# LTE.net
KiCad netlist of a schematic drawn in Altium Designer
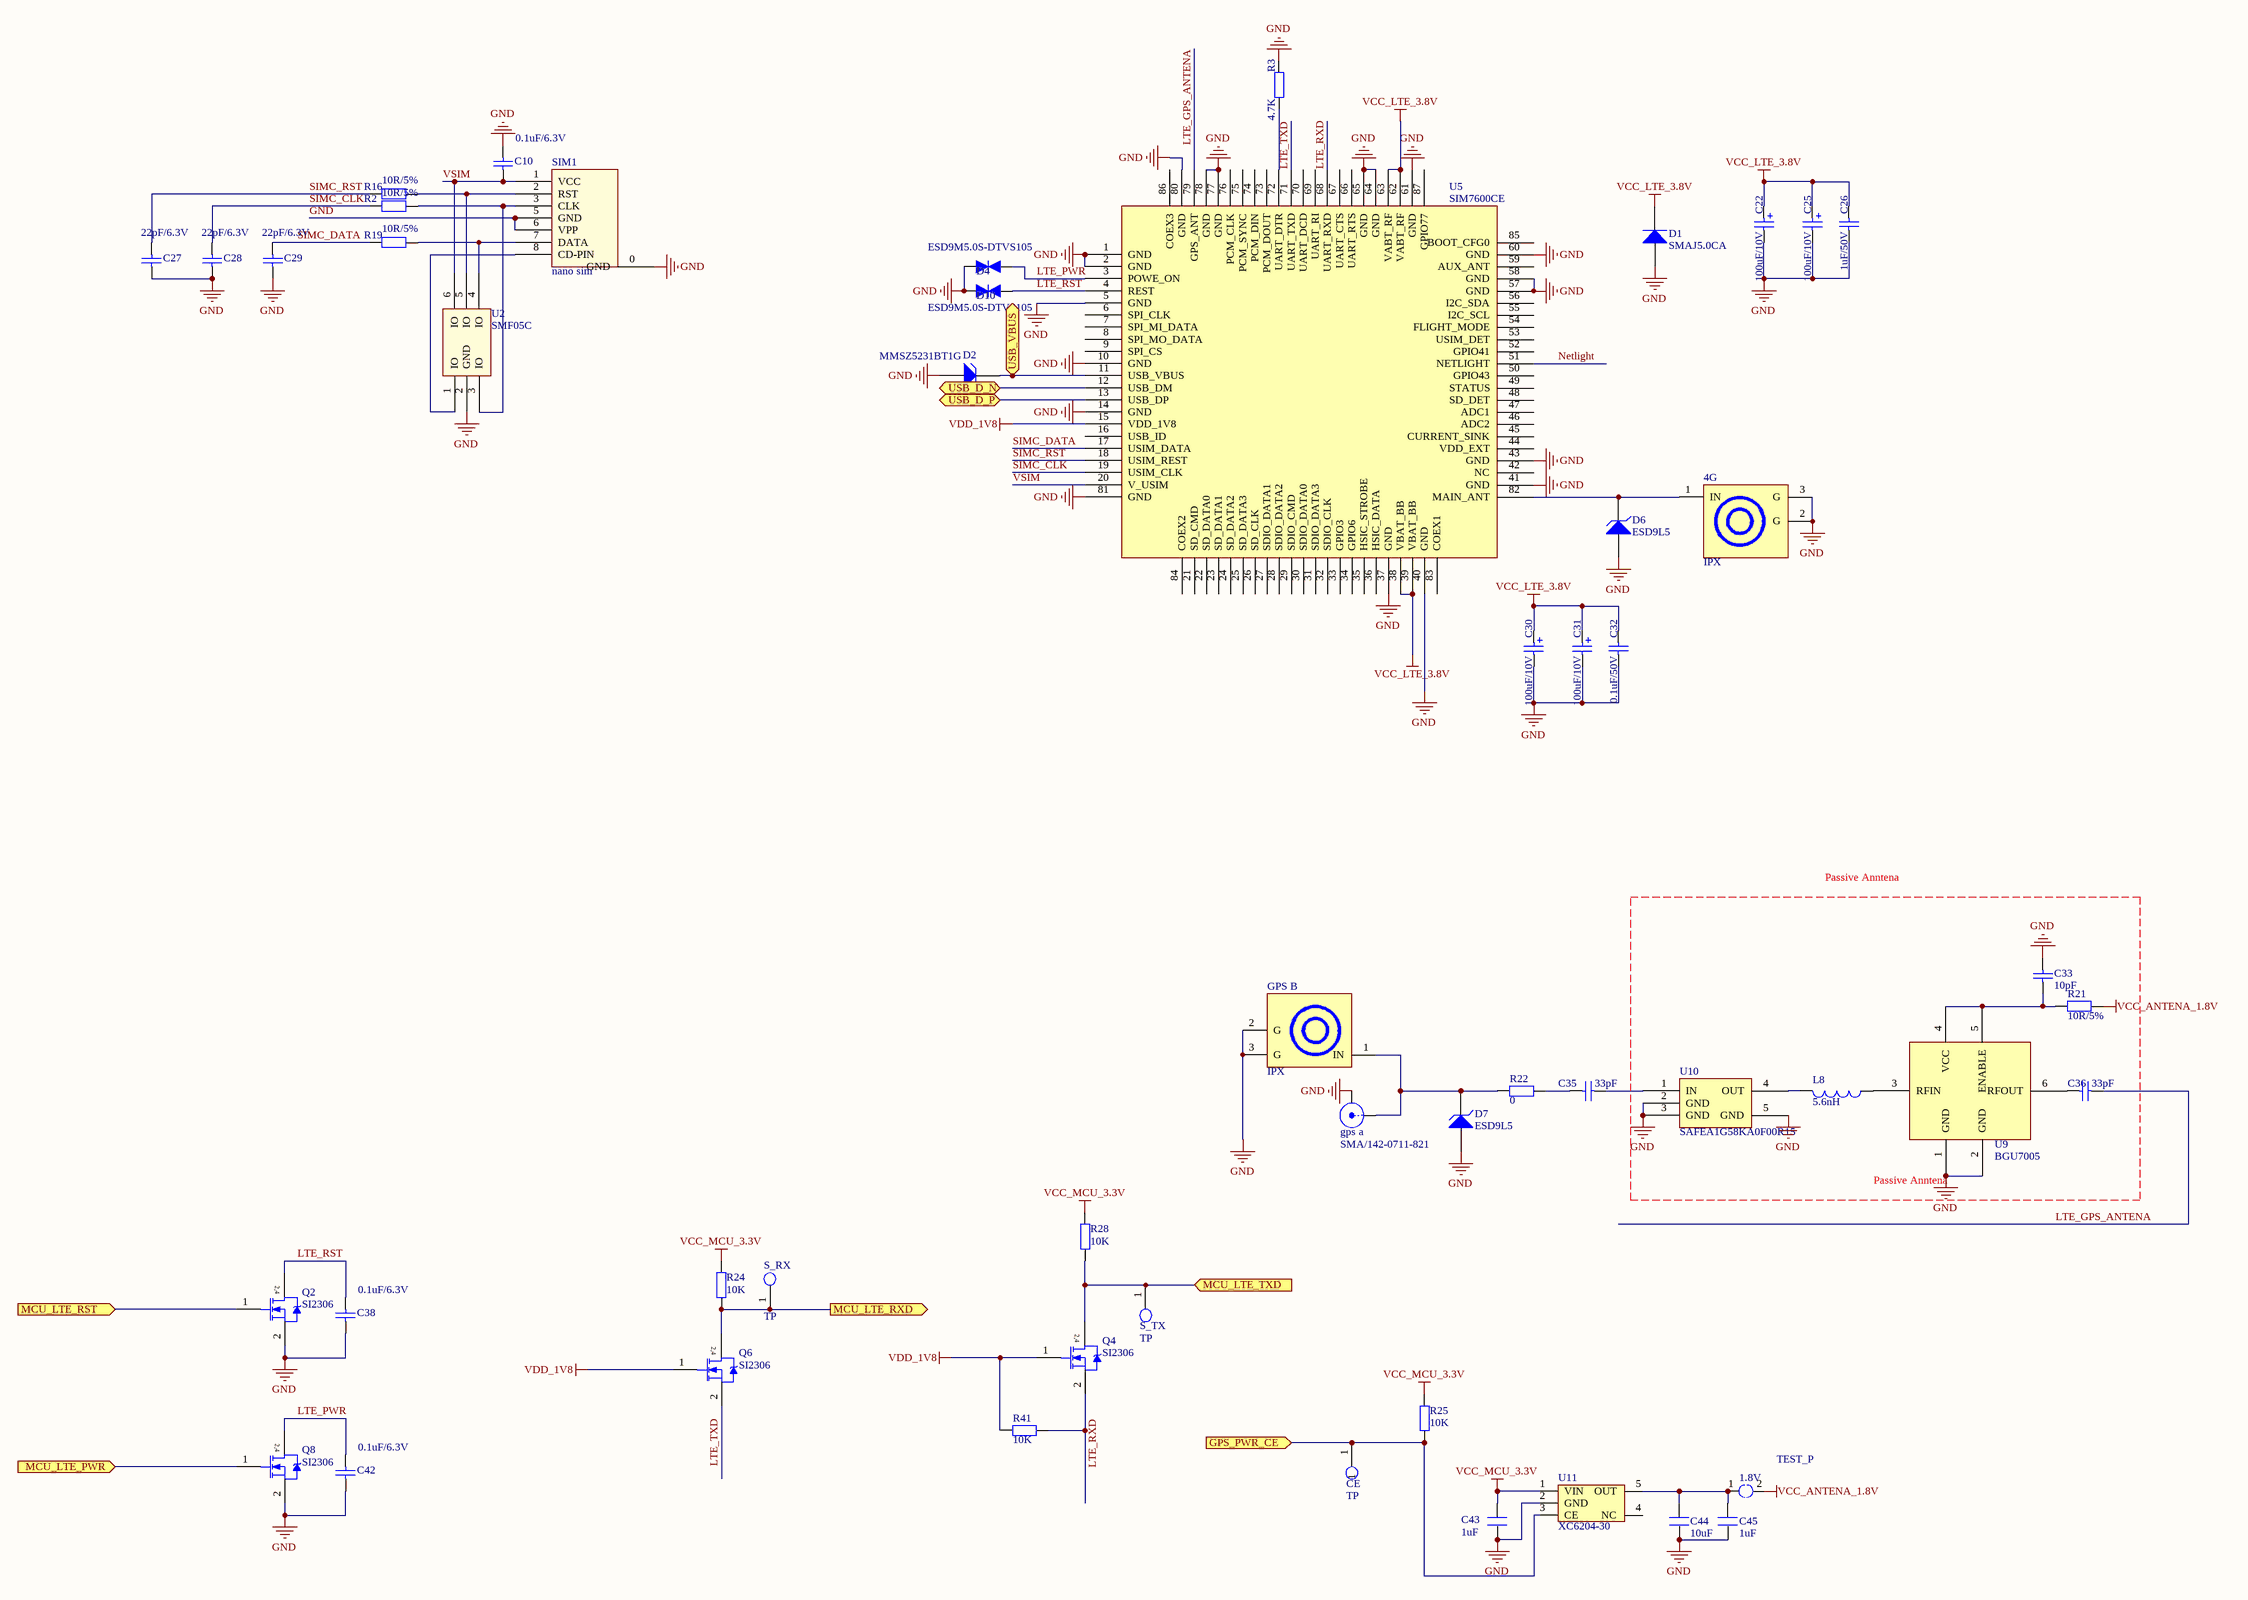
[diagram p0: LTE.SchDoc]

(export (version "E")
  (design (tool "Eeschema 10.0.6"))
  (components
    (comp (ref "1.8V")
      (value "TEST_P")
      (footprint "Pcblib_20110825:TP_High PWR")
      (libsource (lib "Schlib_20110825") (part "TEST_P"))
    )
    (comp (ref "4G")
      (value "IPX")
      (footprint "Pcblib_20110825:ECT8180001581")
      (description "MCU")
      (libsource (lib "MCU") (part "IPX"))
    )
    (comp (ref "C10")
      (value "0.1uF/6.3V")
      (footprint "Pcblib_20110825:0603C")
      (description "Capacitor")
      (fields (field (name "PUBLISHER") "Altium Limited"))
      (libsource (lib "Miscellaneous Devices") (part "Cap"))
    )
    (comp (ref "C22")
      (value "100uF/10V")
      (footprint "1210E")
      (description "Polarized Capacitor (Axial)")
      (fields (field (name "PUBLISHER") "Altium Limited"))
      (libsource (lib "Miscellaneous Devices") (part "Cap Pol2"))
    )
    (comp (ref "C25")
      (value "100uF/10V")
      (footprint "1210E")
      (description "Polarized Capacitor (Axial)")
      (fields (field (name "PUBLISHER") "Altium Limited"))
      (libsource (lib "Miscellaneous Devices") (part "Cap Pol2"))
    )
    (comp (ref "C26")
      (value "1uF/50V")
      (footprint "0603C")
      (description "Capacitor")
      (fields (field (name "PUBLISHER") "Altium Limited"))
      (libsource (lib "Miscellaneous Devices") (part "Cap"))
    )
    (comp (ref "C27")
      (value "22pF/6.3V")
      (footprint "Pcblib_20110825:0603C")
      (description "Capacitor")
      (fields (field (name "PUBLISHER") "Altium Limited"))
      (libsource (lib "Miscellaneous Devices") (part "Cap"))
    )
    (comp (ref "C28")
      (value "22pF/6.3V")
      (footprint "Pcblib_20110825:0603C")
      (description "Capacitor")
      (fields (field (name "PUBLISHER") "Altium Limited"))
      (libsource (lib "Miscellaneous Devices") (part "Cap"))
    )
    (comp (ref "C29")
      (value "22pF/6.3V")
      (footprint "Pcblib_20110825:0603C")
      (description "Capacitor")
      (fields (field (name "PUBLISHER") "Altium Limited"))
      (libsource (lib "Miscellaneous Devices") (part "Cap"))
    )
    (comp (ref "C30")
      (value "100uF/10V")
      (footprint "1210E")
      (description "Polarized Capacitor (Axial)")
      (fields (field (name "PUBLISHER") "Altium Limited"))
      (libsource (lib "Miscellaneous Devices") (part "Cap Pol2"))
    )
    (comp (ref "C31")
      (value "100uF/10V")
      (footprint "1210E")
      (description "Polarized Capacitor (Axial)")
      (fields (field (name "PUBLISHER") "Altium Limited"))
      (libsource (lib "Miscellaneous Devices") (part "Cap Pol2"))
    )
    (comp (ref "C32")
      (value "0.1uF/50V")
      (footprint "0603C")
      (description "Capacitor")
      (fields (field (name "PUBLISHER") "Altium Limited"))
      (libsource (lib "Miscellaneous Devices") (part "Cap"))
    )
    (comp (ref "C33")
      (value "10pF")
      (footprint "Pcblib_20110825:0603C")
      (description "Capacitor")
      (fields (field (name "PUBLISHER") "Altium Limited"))
      (libsource (lib "Miscellaneous Devices") (part "Cap"))
    )
    (comp (ref "C35")
      (value "33pF")
      (footprint "Pcblib_20110825:0603C")
      (description "Capacitor")
      (fields (field (name "PUBLISHER") "Altium Limited"))
      (libsource (lib "Miscellaneous Devices") (part "Cap"))
    )
    (comp (ref "C36")
      (value "33pF")
      (footprint "Pcblib_20110825:0603C")
      (description "Capacitor")
      (fields (field (name "PUBLISHER") "Altium Limited"))
      (libsource (lib "Miscellaneous Devices") (part "Cap"))
    )
    (comp (ref "C38")
      (value "0.1uF/6.3V")
      (footprint "Pcblib_20110825:0603C")
      (description "Capacitor")
      (fields (field (name "PUBLISHER") "Altium Limited"))
      (libsource (lib "Miscellaneous Devices") (part "Cap"))
    )
    (comp (ref "C42")
      (value "0.1uF/6.3V")
      (footprint "Pcblib_20110825:0603C")
      (description "Capacitor")
      (fields (field (name "PUBLISHER") "Altium Limited"))
      (libsource (lib "Miscellaneous Devices") (part "Cap"))
    )
    (comp (ref "C43") (value "1uF") (footprint "0603C") (libsource (lib "MiniFly ") (part "C")))
    (comp (ref "C44") (value "10uF") (footprint "0603C") (libsource (lib "MiniFly ") (part "C")))
    (comp (ref "C45") (value "1uF") (footprint "0402C") (libsource (lib "MiniFly ") (part "C")))
    (comp (ref "CE") (value "TP") (footprint "Pcblib_20110825:TPD") (libsource (lib "") (part "TP_1")))
    (comp (ref "D1")
      (value "SMAJ5.0CA")
      (footprint "SMA")
      (description "Default Diode")
      (fields (field (name "PUBLISHER") "Altium Limited"))
      (libsource (lib "Miscellaneous Devices") (part "Diode"))
    )
    (comp (ref "D2")
      (value "MMSZ5231BT1G")
      (footprint "Pcblib_20110825:SOD123")
      (description "Zener Diode")
      (fields (field (name "PUBLISHER") "Altium Limited"))
      (libsource (lib "Miscellaneous Devices") (part "D Zener"))
    )
    (comp (ref "D4")
      (value "ESD9M5.0S-DTVS105")
      (footprint "SOD923")
      (libsource (lib "Schlib_20110825") (part "ESD9M5.0S-DTVS105"))
    )
    (comp (ref "D6")
      (value "ESD9L5")
      (footprint "Pcblib_20110825:SOD923")
      (description "Zener Diode")
      (fields (field (name "PUBLISHER") "Altium Limited"))
      (libsource (lib "Miscellaneous Devices") (part "D Zener"))
    )
    (comp (ref "D7")
      (value "ESD9L5")
      (footprint "Pcblib_20110825:SOD923")
      (description "Zener Diode")
      (fields (field (name "PUBLISHER") "Altium Limited"))
      (libsource (lib "Miscellaneous Devices") (part "D Zener"))
    )
    (comp (ref "D10")
      (value "ESD9M5.0S-DTVS105")
      (footprint "SOD923")
      (libsource (lib "Schlib_20110825") (part "ESD9M5.0S-DTVS105"))
    )
    (comp (ref "gps a")
      (value "SMA/142-0711-821")
      (footprint "Pcblib_20110825:SMA END LAUNCH JACK RECEPTACLE SHORT")
      (description "SMA Straight Connector")
      (fields (field (name "PUBLISHER") "Altium Limited"))
      (libsource (lib "SX1276_e266v02a") (part "SMA"))
    )
    (comp (ref "GPS B")
      (value "IPX")
      (footprint "Pcblib_20110825:ECT8180001581")
      (description "MCU")
      (libsource (lib "") (part "IPX_1"))
    )
    (comp (ref "L8")
      (value "5.6nH")
      (footprint "INDC1005AL")
      (description "Inductor")
      (fields (field (name "PUBLISHER") "Altium Limited"))
      (libsource (lib "Miscellaneous Devices") (part "Inductor"))
    )
    (comp (ref "Q2")
      (value "SI2306")
      (footprint "Pcblib_20110825:SOT23-3")
      (description "BUK92150-55A")
      (fields (field (name "PUBLISHER") "Altium Limited"))
      (libsource (lib "Schlib1") (part "BUK92150-55A"))
    )
    (comp (ref "Q4")
      (value "SI2306")
      (footprint "Pcblib_20110825:SOT23-3")
      (description "BUK92150-55A")
      (fields (field (name "PUBLISHER") "Altium Limited"))
      (libsource (lib "Schlib1") (part "BUK92150-55A"))
    )
    (comp (ref "Q6")
      (value "SI2306")
      (footprint "Pcblib_20110825:SOT23-3")
      (description "BUK92150-55A")
      (fields (field (name "PUBLISHER") "Altium Limited"))
      (libsource (lib "Schlib1") (part "BUK92150-55A"))
    )
    (comp (ref "Q8")
      (value "SI2306")
      (footprint "Pcblib_20110825:SOT23-3")
      (description "BUK92150-55A")
      (fields (field (name "PUBLISHER") "Altium Limited"))
      (libsource (lib "Schlib1") (part "BUK92150-55A"))
    )
    (comp (ref "R2")
      (value "10R/5%")
      (footprint "Pcblib_20110825:0603R")
      (description "Resistor")
      (fields (field (name "PUBLISHER") "Altium Limited"))
      (libsource (lib "") (part "Res2_1"))
    )
    (comp (ref "R3")
      (value "4.7K")
      (footprint "Pcblib_20110825:0603R")
      (description "Resistor")
      (fields (field (name "PUBLISHER") "Altium Limited"))
      (libsource (lib "") (part "Res2_3"))
    )
    (comp (ref "R16")
      (value "10R/5%")
      (footprint "Pcblib_20110825:0603R")
      (description "Resistor")
      (fields (field (name "PUBLISHER") "Altium Limited"))
      (libsource (lib "") (part "Res2_1"))
    )
    (comp (ref "R19")
      (value "10R/5%")
      (footprint "Pcblib_20110825:0603R")
      (description "Resistor")
      (fields (field (name "PUBLISHER") "Altium Limited"))
      (libsource (lib "") (part "Res2_1"))
    )
    (comp (ref "R21")
      (value "10R/5%")
      (footprint "Pcblib_20110825:0603R")
      (description "Resistor")
      (fields (field (name "PUBLISHER") "Altium Limited"))
      (libsource (lib "Miscellaneous Devices") (part "Res2"))
    )
    (comp (ref "R22")
      (value "0")
      (footprint "Pcblib_20110825:0603R")
      (description "Resistor")
      (fields (field (name "PUBLISHER") "Altium Limited"))
      (libsource (lib "Miscellaneous Devices") (part "Res2"))
    )
    (comp (ref "R24")
      (value "10K")
      (footprint "Pcblib_20110825:0603R")
      (description "Resistor")
      (fields (field (name "PUBLISHER") "Altium Limited"))
      (libsource (lib "") (part "Res2_3"))
    )
    (comp (ref "R25")
      (value "10K")
      (footprint "Pcblib_20110825:0603R")
      (description "Resistor")
      (fields (field (name "PUBLISHER") "Altium Limited"))
      (libsource (lib "") (part "Res2_2"))
    )
    (comp (ref "R28")
      (value "10K")
      (footprint "Pcblib_20110825:0603R")
      (description "Resistor")
      (fields (field (name "PUBLISHER") "Altium Limited"))
      (libsource (lib "") (part "Res2_2"))
    )
    (comp (ref "R41")
      (value "10K")
      (footprint "Pcblib_20110825:0603R")
      (description "Resistor")
      (fields (field (name "PUBLISHER") "Altium Limited"))
      (libsource (lib "") (part "Res2_1"))
    )
    (comp (ref "SIM1") (value "nano sim") (footprint "Nano SIM") (libsource (lib "lm") (part "nano sim")))
    (comp (ref "S_RX")
      (value "TP")
      (footprint "Pcblib_20110825:TPD")
      (libsource (lib "Schlib_20110825") (part "TP"))
    )
    (comp (ref "S_TX")
      (value "TP")
      (footprint "Pcblib_20110825:TPD")
      (libsource (lib "Schlib_20110825") (part "TP"))
    )
    (comp (ref "U2") (value "SMF05C") (footprint "SC70-6L") (libsource (lib "lm") (part "SMF05C")))
    (comp (ref "U5")
      (value "SIM7600CE")
      (footprint "SIM7600CE")
      (libsource (lib "DTU_20161116_ZM_V1.1") (part "SIM7600CE"))
    )
    (comp (ref "U9")
      (value "BGU7005")
      (footprint "BGU7005")
      (libsource (lib "Schlib_20110825") (part "BGU7005"))
    )
    (comp (ref "U10")
      (value "SAFEA1G58KA0F00R15")
      (footprint "SAFEA1G58KA0F00R15")
      (libsource (lib "Schlib_20110825") (part "SAFEA1G58KA0F00R15"))
    )
    (comp (ref "U11")
      (value "XC6204-30")
      (footprint "SOT23-5(DBV)")
      (libsource (lib "MiniFly ") (part "XC6204"))
    )
  )
  (nets
    (net (code "1") (name "/GPS_PWR_CE") (class "Default")
      (node (ref "CE") (pin "1") (pinfunction "1_1") (pintype "passive"))
      (node (ref "R25") (pin "1") (pinfunction "1_1") (pintype "passive"))
      (node (ref "U11") (pin "3") (pinfunction "CE_3") (pintype "passive"))
    )
    (net (code "2") (name "/LTE_GPS_ANTENA") (class "Default")
      (node (ref "C36") (pin "2") (pinfunction "2_2") (pintype "passive"))
      (node (ref "U5") (pin "79") (pinfunction "GPS_ANT_79") (pintype "passive"))
    )
    (net (code "3") (name "/LTE_PWR") (class "Default")
      (node (ref "C42") (pin "1") (pinfunction "1_1") (pintype "passive"))
      (node (ref "D4") (pin "2") (pinfunction "K_2") (pintype "passive"))
      (node (ref "Q8") (pin "3") (pinfunction "D_3") (pintype "passive"))
      (node (ref "U5") (pin "3") (pinfunction "POWE_ON_3") (pintype "passive"))
    )
    (net (code "4") (name "/LTE_RST") (class "Default")
      (node (ref "C38") (pin "1") (pinfunction "1_1") (pintype "passive"))
      (node (ref "D10") (pin "2") (pinfunction "K_2") (pintype "passive"))
      (node (ref "Q2") (pin "3") (pinfunction "D_3") (pintype "passive"))
      (node (ref "U5") (pin "4") (pinfunction "REST_4") (pintype "passive"))
    )
    (net (code "5") (name "/LTE_RXD") (class "Default")
      (node (ref "Q4") (pin "2") (pinfunction "S_2") (pintype "passive"))
      (node (ref "R41") (pin "1") (pinfunction "1_1") (pintype "passive"))
      (node (ref "U5") (pin "68") (pinfunction "UART_RXD_68") (pintype "passive"))
    )
    (net (code "6") (name "/LTE_TXD") (class "Default")
      (node (ref "Q6") (pin "2") (pinfunction "S_2") (pintype "passive"))
      (node (ref "U5") (pin "71") (pinfunction "UART_TXD_71") (pintype "passive"))
    )
    (net (code "7") (name "/MCU_LTE_PWR") (class "Default")
      (node (ref "Q8") (pin "1") (pinfunction "G_1") (pintype "passive"))
    )
    (net (code "8") (name "/MCU_LTE_RST") (class "Default")
      (node (ref "Q2") (pin "1") (pinfunction "G_1") (pintype "passive"))
    )
    (net (code "9") (name "/MCU_LTE_RXD") (class "Default")
      (node (ref "Q6") (pin "3") (pinfunction "D_3") (pintype "passive"))
      (node (ref "R24") (pin "2") (pinfunction "2_2") (pintype "passive"))
      (node (ref "S_RX") (pin "1") (pintype "passive"))
    )
    (net (code "10") (name "/MCU_LTE_TXD") (class "Default")
      (node (ref "Q4") (pin "3") (pinfunction "D_3") (pintype "passive"))
      (node (ref "R28") (pin "1") (pinfunction "1_1") (pintype "passive"))
      (node (ref "S_TX") (pin "1") (pintype "passive"))
    )
    (net (code "11") (name "/Netlight") (class "Default")
      (node (ref "U5") (pin "51") (pinfunction "NETLIGHT_51") (pintype "passive"))
    )
    (net (code "12") (name "/SIMC_CLK") (class "Default")
      (node (ref "C28") (pin "1") (pinfunction "1_1") (pintype "passive"))
      (node (ref "R2") (pin "2") (pinfunction "2_2") (pintype "passive"))
      (node (ref "U5") (pin "19") (pinfunction "USIM_CLK_19") (pintype "passive"))
    )
    (net (code "13") (name "/SIMC_DATA") (class "Default")
      (node (ref "C29") (pin "1") (pinfunction "1_1") (pintype "passive"))
      (node (ref "R19") (pin "2") (pinfunction "2_2") (pintype "passive"))
      (node (ref "U5") (pin "17") (pinfunction "USIM_DATA_17") (pintype "passive"))
    )
    (net (code "14") (name "/SIMC_RST") (class "Default")
      (node (ref "C27") (pin "1") (pinfunction "1_1") (pintype "passive"))
      (node (ref "R16") (pin "2") (pinfunction "2_2") (pintype "passive"))
      (node (ref "U5") (pin "18") (pinfunction "USIM_REST_18") (pintype "passive"))
    )
    (net (code "15") (name "/USB_D_N") (class "Default")
      (node (ref "U5") (pin "12") (pinfunction "USB_DM_12") (pintype "passive"))
    )
    (net (code "16") (name "/USB_D_P") (class "Default")
      (node (ref "U5") (pin "13") (pinfunction "USB_DP_13") (pintype "passive"))
    )
    (net (code "17") (name "/USB_VBUS") (class "Default")
      (node (ref "D2") (pin "K") (pinfunction "K_K") (pintype "passive"))
      (node (ref "U5") (pin "11") (pinfunction "USB_VBUS_11") (pintype "passive"))
    )
    (net (code "18") (name "/VSIM") (class "Default")
      (node (ref "C10") (pin "2") (pinfunction "2_2") (pintype "passive"))
      (node (ref "SIM1") (pin "1") (pinfunction "VCC_1") (pintype "passive"))
      (node (ref "U2") (pin "6") (pinfunction "IO_6") (pintype "passive"))
      (node (ref "U5") (pin "20") (pinfunction "V_USIM_20") (pintype "passive"))
    )
    (net (code "19") (name "GND") (class "Default")
      (node (ref "4G") (pin "2") (pinfunction "G_2") (pintype "passive"))
      (node (ref "4G") (pin "3") (pinfunction "G_3") (pintype "passive"))
      (node (ref "C10") (pin "1") (pinfunction "1_1") (pintype "passive"))
      (node (ref "C22") (pin "2") (pinfunction "2_2") (pintype "passive"))
      (node (ref "C25") (pin "2") (pinfunction "2_2") (pintype "passive"))
      (node (ref "C26") (pin "2") (pinfunction "2_2") (pintype "passive"))
      (node (ref "C27") (pin "2") (pinfunction "2_2") (pintype "passive"))
      (node (ref "C28") (pin "2") (pinfunction "2_2") (pintype "passive"))
      (node (ref "C29") (pin "2") (pinfunction "2_2") (pintype "passive"))
      (node (ref "C30") (pin "2") (pinfunction "2_2") (pintype "passive"))
      (node (ref "C31") (pin "2") (pinfunction "2_2") (pintype "passive"))
      (node (ref "C32") (pin "2") (pinfunction "2_2") (pintype "passive"))
      (node (ref "C33") (pin "2") (pinfunction "2_2") (pintype "passive"))
      (node (ref "C38") (pin "2") (pinfunction "2_2") (pintype "passive"))
      (node (ref "C42") (pin "2") (pinfunction "2_2") (pintype "passive"))
      (node (ref "C43") (pin "1") (pintype "passive"))
      (node (ref "C44") (pin "1") (pintype "passive"))
      (node (ref "C45") (pin "1") (pintype "passive"))
      (node (ref "D1") (pin "1") (pinfunction "A_1") (pintype "passive"))
      (node (ref "D10") (pin "1") (pinfunction "A_1") (pintype "passive"))
      (node (ref "D2") (pin "A") (pinfunction "A_A") (pintype "passive"))
      (node (ref "D4") (pin "1") (pinfunction "A_1") (pintype "passive"))
      (node (ref "D6") (pin "A") (pinfunction "A_A") (pintype "passive"))
      (node (ref "D7") (pin "A") (pinfunction "A_A") (pintype "passive"))
      (node (ref "GPS B") (pin "2") (pinfunction "G_2") (pintype "passive"))
      (node (ref "GPS B") (pin "3") (pinfunction "G_3") (pintype "passive"))
      (node (ref "Q2") (pin "2") (pinfunction "S_2") (pintype "passive"))
      (node (ref "Q8") (pin "2") (pinfunction "S_2") (pintype "passive"))
      (node (ref "R3") (pin "1") (pinfunction "1_1") (pintype "passive"))
      (node (ref "SIM1") (pin "0") (pinfunction "GND_0") (pintype "passive"))
      (node (ref "SIM1") (pin "5") (pinfunction "GND_5") (pintype "passive"))
      (node (ref "SIM1") (pin "6") (pinfunction "VPP_6") (pintype "passive"))
      (node (ref "U10") (pin "2") (pinfunction "GND_2") (pintype "passive"))
      (node (ref "U10") (pin "3") (pinfunction "GND_3") (pintype "passive"))
      (node (ref "U10") (pin "5") (pinfunction "GND_5") (pintype "passive"))
      (node (ref "U11") (pin "2") (pinfunction "GND_2") (pintype "passive"))
      (node (ref "U2") (pin "2") (pinfunction "GND_2") (pintype "passive"))
      (node (ref "U5") (pin "1") (pinfunction "GND_1") (pintype "passive"))
      (node (ref "U5") (pin "10") (pinfunction "GND_10") (pintype "passive"))
      (node (ref "U5") (pin "14") (pinfunction "GND_14") (pintype "passive"))
      (node (ref "U5") (pin "2") (pinfunction "GND_2") (pintype "passive"))
      (node (ref "U5") (pin "37") (pinfunction "GND_37") (pintype "passive"))
      (node (ref "U5") (pin "40") (pinfunction "GND_40") (pintype "passive"))
      (node (ref "U5") (pin "41") (pinfunction "GND_41") (pintype "passive"))
      (node (ref "U5") (pin "43") (pinfunction "GND_43") (pintype "passive"))
      (node (ref "U5") (pin "5") (pinfunction "GND_5") (pintype "passive"))
      (node (ref "U5") (pin "57") (pinfunction "GND_57") (pintype "passive"))
      (node (ref "U5") (pin "58") (pinfunction "GND_58") (pintype "passive"))
      (node (ref "U5") (pin "60") (pinfunction "GND_60") (pintype "passive"))
      (node (ref "U5") (pin "61") (pinfunction "GND_61") (pintype "passive"))
      (node (ref "U5") (pin "64") (pinfunction "GND_64") (pintype "passive"))
      (node (ref "U5") (pin "65") (pinfunction "GND_65") (pintype "passive"))
      (node (ref "U5") (pin "77") (pinfunction "GND_77") (pintype "passive"))
      (node (ref "U5") (pin "78") (pinfunction "GND_78") (pintype "passive"))
      (node (ref "U5") (pin "80") (pinfunction "GND_80") (pintype "passive"))
      (node (ref "U5") (pin "81") (pinfunction "GND_81") (pintype "passive"))
      (node (ref "U9") (pin "1") (pinfunction "GND_1") (pintype "passive"))
      (node (ref "U9") (pin "2") (pinfunction "GND_2") (pintype "passive"))
      (node (ref "gps a") (pin "2") (pinfunction "GND_2") (pintype "passive"))
    )
    (net (code "20") (name "Net-(4G-IN)") (class "Default")
      (node (ref "4G") (pin "1") (pinfunction "IN_1") (pintype "passive"))
      (node (ref "D6") (pin "K") (pinfunction "K_K") (pintype "passive"))
      (node (ref "U5") (pin "82") (pinfunction "MAIN_ANT_82") (pintype "passive"))
    )
    (net (code "21") (name "Net-(C35-Pad1)") (class "Default")
      (node (ref "C35") (pin "1") (pinfunction "1_1") (pintype "passive"))
      (node (ref "R22") (pin "2") (pinfunction "2_2") (pintype "passive"))
    )
    (net (code "22") (name "Net-(GPS B-IN)") (class "Default")
      (node (ref "D7") (pin "K") (pinfunction "K_K") (pintype "passive"))
      (node (ref "GPS B") (pin "1") (pinfunction "IN_1") (pintype "passive"))
      (node (ref "R22") (pin "1") (pinfunction "1_1") (pintype "passive"))
      (node (ref "gps a") (pin "1") (pinfunction "Signal_1") (pintype "passive"))
    )
    (net (code "23") (name "Net-(SIM1-CD-PIN)") (class "Default")
      (node (ref "SIM1") (pin "8") (pinfunction "CD-PIN_8") (pintype "passive"))
      (node (ref "U2") (pin "1") (pinfunction "IO_1") (pintype "passive"))
    )
    (net (code "24") (name "Net-(SIM1-CLK)") (class "Default")
      (node (ref "R2") (pin "1") (pinfunction "1_1") (pintype "passive"))
      (node (ref "SIM1") (pin "3") (pinfunction "CLK_3") (pintype "passive"))
      (node (ref "U2") (pin "3") (pinfunction "IO_3") (pintype "passive"))
    )
    (net (code "25") (name "Net-(SIM1-DATA)") (class "Default")
      (node (ref "R19") (pin "1") (pinfunction "1_1") (pintype "passive"))
      (node (ref "SIM1") (pin "7") (pinfunction "DATA_7") (pintype "passive"))
      (node (ref "U2") (pin "4") (pinfunction "IO_4") (pintype "passive"))
    )
    (net (code "26") (name "Net-(SIM1-RST)") (class "Default")
      (node (ref "R16") (pin "1") (pinfunction "1_1") (pintype "passive"))
      (node (ref "SIM1") (pin "2") (pinfunction "RST_2") (pintype "passive"))
      (node (ref "U2") (pin "5") (pinfunction "IO_5") (pintype "passive"))
    )
    (net (code "27") (name "Net-(U5-UART_DTR)") (class "Default")
      (node (ref "R3") (pin "2") (pinfunction "2_2") (pintype "passive"))
      (node (ref "U5") (pin "72") (pinfunction "UART_DTR_72") (pintype "passive"))
    )
    (net (code "28") (name "Net-(U9-ENABLE)") (class "Default")
      (node (ref "C33") (pin "1") (pinfunction "1_1") (pintype "passive"))
      (node (ref "R21") (pin "1") (pinfunction "1_1") (pintype "passive"))
      (node (ref "U9") (pin "4") (pinfunction "VCC_4") (pintype "passive"))
      (node (ref "U9") (pin "5") (pinfunction "ENABLE_5") (pintype "passive"))
    )
    (net (code "29") (name "Net-(U9-RFIN)") (class "Default")
      (node (ref "L8") (pin "1") (pinfunction "1_1") (pintype "passive"))
      (node (ref "U9") (pin "3") (pinfunction "RFIN_3") (pintype "passive"))
    )
    (net (code "30") (name "Net-(U9-RFOUT)") (class "Default")
      (node (ref "C36") (pin "1") (pinfunction "1_1") (pintype "passive"))
      (node (ref "U9") (pin "6") (pinfunction "RFOUT_6") (pintype "passive"))
    )
    (net (code "31") (name "Net-(U10-IN)") (class "Default")
      (node (ref "C35") (pin "2") (pinfunction "2_2") (pintype "passive"))
      (node (ref "U10") (pin "1") (pinfunction "IN_1") (pintype "passive"))
    )
    (net (code "32") (name "Net-(U10-OUT)") (class "Default")
      (node (ref "L8") (pin "2") (pinfunction "2_2") (pintype "passive"))
      (node (ref "U10") (pin "4") (pinfunction "OUT_4") (pintype "passive"))
    )
    (net (code "33") (name "Net-(U11-OUT)") (class "Default")
      (node (ref "1.8V") (pin "1") (pinfunction "1_1") (pintype "passive"))
      (node (ref "C44") (pin "2") (pintype "passive"))
      (node (ref "C45") (pin "2") (pintype "passive"))
      (node (ref "U11") (pin "5") (pinfunction "OUT_5") (pintype "passive"))
    )
    (net (code "34") (name "VCC_ANTENA_1.8V") (class "Default")
      (node (ref "1.8V") (pin "2") (pinfunction "2_2") (pintype "passive"))
      (node (ref "R21") (pin "2") (pinfunction "2_2") (pintype "passive"))
    )
    (net (code "35") (name "VCC_LTE_3.8V") (class "Default")
      (node (ref "C22") (pin "1") (pinfunction "1_1") (pintype "passive"))
      (node (ref "C25") (pin "1") (pinfunction "1_1") (pintype "passive"))
      (node (ref "C26") (pin "1") (pinfunction "1_1") (pintype "passive"))
      (node (ref "C30") (pin "1") (pinfunction "1_1") (pintype "passive"))
      (node (ref "C31") (pin "1") (pinfunction "1_1") (pintype "passive"))
      (node (ref "C32") (pin "1") (pinfunction "1_1") (pintype "passive"))
      (node (ref "D1") (pin "2") (pinfunction "K_2") (pintype "passive"))
      (node (ref "U5") (pin "38") (pinfunction "VBAT_BB_38") (pintype "passive"))
      (node (ref "U5") (pin "39") (pinfunction "VBAT_BB_39") (pintype "passive"))
      (node (ref "U5") (pin "62") (pinfunction "VABT_RF_62") (pintype "passive"))
      (node (ref "U5") (pin "63") (pinfunction "VABT_RF_63") (pintype "passive"))
    )
    (net (code "36") (name "VCC_MCU_3.3V") (class "Default")
      (node (ref "C43") (pin "2") (pintype "passive"))
      (node (ref "R24") (pin "1") (pinfunction "1_1") (pintype "passive"))
      (node (ref "R25") (pin "2") (pinfunction "2_2") (pintype "passive"))
      (node (ref "R28") (pin "2") (pinfunction "2_2") (pintype "passive"))
      (node (ref "U11") (pin "1") (pinfunction "VIN_1") (pintype "passive"))
    )
    (net (code "37") (name "VDD_1V8") (class "Default")
      (node (ref "Q4") (pin "1") (pinfunction "G_1") (pintype "passive"))
      (node (ref "Q6") (pin "1") (pinfunction "G_1") (pintype "passive"))
      (node (ref "R41") (pin "2") (pinfunction "2_2") (pintype "passive"))
      (node (ref "U5") (pin "15") (pinfunction "VDD_1V8_15") (pintype "passive"))
    )
    (net (code "38") (name "unconnected-(U5-ADC1-Pad47)") (class "Default")
      (node (ref "U5") (pin "47") (pinfunction "ADC1_47") (pintype "passive"))
    )
    (net (code "39") (name "unconnected-(U5-ADC2-Pad46)") (class "Default")
      (node (ref "U5") (pin "46") (pinfunction "ADC2_46") (pintype "passive"))
    )
    (net (code "40") (name "unconnected-(U5-AUX_ANT-Pad59)") (class "Default")
      (node (ref "U5") (pin "59") (pinfunction "AUX_ANT_59") (pintype "passive"))
    )
    (net (code "41") (name "unconnected-(U5-BOOT_CFG0-Pad85)") (class "Default")
      (node (ref "U5") (pin "85") (pinfunction "BOOT_CFG0_85") (pintype "passive"))
    )
    (net (code "42") (name "unconnected-(U5-COEX1-Pad83)") (class "Default")
      (node (ref "U5") (pin "83") (pinfunction "COEX1_83") (pintype "passive"))
    )
    (net (code "43") (name "unconnected-(U5-COEX2-Pad84)") (class "Default")
      (node (ref "U5") (pin "84") (pinfunction "COEX2_84") (pintype "passive"))
    )
    (net (code "44") (name "unconnected-(U5-COEX3-Pad86)") (class "Default")
      (node (ref "U5") (pin "86") (pinfunction "COEX3_86") (pintype "passive"))
    )
    (net (code "45") (name "unconnected-(U5-CURRENT_SINK-Pad45)") (class "Default")
      (node (ref "U5") (pin "45") (pinfunction "CURRENT_SINK_45") (pintype "passive"))
    )
    (net (code "46") (name "unconnected-(U5-FLIGHT_MODE-Pad54)") (class "Default")
      (node (ref "U5") (pin "54") (pinfunction "FLIGHT_MODE_54") (pintype "passive"))
    )
    (net (code "47") (name "unconnected-(U5-GPIO3-Pad33)") (class "Default")
      (node (ref "U5") (pin "33") (pinfunction "GPIO3_33") (pintype "passive"))
    )
    (net (code "48") (name "unconnected-(U5-GPIO6-Pad34)") (class "Default")
      (node (ref "U5") (pin "34") (pinfunction "GPIO6_34") (pintype "passive"))
    )
    (net (code "49") (name "unconnected-(U5-GPIO41-Pad52)") (class "Default")
      (node (ref "U5") (pin "52") (pinfunction "GPIO41_52") (pintype "passive"))
    )
    (net (code "50") (name "unconnected-(U5-GPIO43-Pad50)") (class "Default")
      (node (ref "U5") (pin "50") (pinfunction "GPIO43_50") (pintype "passive"))
    )
    (net (code "51") (name "unconnected-(U5-GPIO77-Pad87)") (class "Default")
      (node (ref "U5") (pin "87") (pinfunction "GPIO77_87") (pintype "passive"))
    )
    (net (code "52") (name "unconnected-(U5-HSIC_DATA-Pad36)") (class "Default")
      (node (ref "U5") (pin "36") (pinfunction "HSIC_DATA_36") (pintype "passive"))
    )
    (net (code "53") (name "unconnected-(U5-HSIC_STROBE-Pad35)") (class "Default")
      (node (ref "U5") (pin "35") (pinfunction "HSIC_STROBE_35") (pintype "passive"))
    )
    (net (code "54") (name "unconnected-(U5-I2C_SCL-Pad55)") (class "Default")
      (node (ref "U5") (pin "55") (pinfunction "I2C_SCL_55") (pintype "passive"))
    )
    (net (code "55") (name "unconnected-(U5-I2C_SDA-Pad56)") (class "Default")
      (node (ref "U5") (pin "56") (pinfunction "I2C_SDA_56") (pintype "passive"))
    )
    (net (code "56") (name "unconnected-(U5-NC-Pad42)") (class "Default")
      (node (ref "U5") (pin "42") (pinfunction "NC_42") (pintype "passive"))
    )
    (net (code "57") (name "unconnected-(U5-PCM_CLK-Pad76)") (class "Default")
      (node (ref "U5") (pin "76") (pinfunction "PCM_CLK_76") (pintype "passive"))
    )
    (net (code "58") (name "unconnected-(U5-PCM_DIN-Pad74)") (class "Default")
      (node (ref "U5") (pin "74") (pinfunction "PCM_DIN_74") (pintype "passive"))
    )
    (net (code "59") (name "unconnected-(U5-PCM_DOUT-Pad73)") (class "Default")
      (node (ref "U5") (pin "73") (pinfunction "PCM_DOUT_73") (pintype "passive"))
    )
    (net (code "60") (name "unconnected-(U5-PCM_SYNC-Pad75)") (class "Default")
      (node (ref "U5") (pin "75") (pinfunction "PCM_SYNC_75") (pintype "passive"))
    )
    (net (code "61") (name "unconnected-(U5-SDIO_CLK-Pad32)") (class "Default")
      (node (ref "U5") (pin "32") (pinfunction "SDIO_CLK_32") (pintype "passive"))
    )
    (net (code "62") (name "unconnected-(U5-SDIO_CMD-Pad29)") (class "Default")
      (node (ref "U5") (pin "29") (pinfunction "SDIO_CMD_29") (pintype "passive"))
    )
    (net (code "63") (name "unconnected-(U5-SDIO_DATA0-Pad30)") (class "Default")
      (node (ref "U5") (pin "30") (pinfunction "SDIO_DATA0_30") (pintype "passive"))
    )
    (net (code "64") (name "unconnected-(U5-SDIO_DATA1-Pad27)") (class "Default")
      (node (ref "U5") (pin "27") (pinfunction "SDIO_DATA1_27") (pintype "passive"))
    )
    (net (code "65") (name "unconnected-(U5-SDIO_DATA2-Pad28)") (class "Default")
      (node (ref "U5") (pin "28") (pinfunction "SDIO_DATA2_28") (pintype "passive"))
    )
    (net (code "66") (name "unconnected-(U5-SDIO_DATA3-Pad31)") (class "Default")
      (node (ref "U5") (pin "31") (pinfunction "SDIO_DATA3_31") (pintype "passive"))
    )
    (net (code "67") (name "unconnected-(U5-SD_CLK-Pad26)") (class "Default")
      (node (ref "U5") (pin "26") (pinfunction "SD_CLK_26") (pintype "passive"))
    )
    (net (code "68") (name "unconnected-(U5-SD_CMD-Pad21)") (class "Default")
      (node (ref "U5") (pin "21") (pinfunction "SD_CMD_21") (pintype "passive"))
    )
    (net (code "69") (name "unconnected-(U5-SD_DATA0-Pad22)") (class "Default")
      (node (ref "U5") (pin "22") (pinfunction "SD_DATA0_22") (pintype "passive"))
    )
    (net (code "70") (name "unconnected-(U5-SD_DATA1-Pad23)") (class "Default")
      (node (ref "U5") (pin "23") (pinfunction "SD_DATA1_23") (pintype "passive"))
    )
    (net (code "71") (name "unconnected-(U5-SD_DATA2-Pad24)") (class "Default")
      (node (ref "U5") (pin "24") (pinfunction "SD_DATA2_24") (pintype "passive"))
    )
    (net (code "72") (name "unconnected-(U5-SD_DATA3-Pad25)") (class "Default")
      (node (ref "U5") (pin "25") (pinfunction "SD_DATA3_25") (pintype "passive"))
    )
    (net (code "73") (name "unconnected-(U5-SD_DET-Pad48)") (class "Default")
      (node (ref "U5") (pin "48") (pinfunction "SD_DET_48") (pintype "passive"))
    )
    (net (code "74") (name "unconnected-(U5-SPI_CLK-Pad6)") (class "Default")
      (node (ref "U5") (pin "6") (pinfunction "SPI_CLK_6") (pintype "passive"))
    )
    (net (code "75") (name "unconnected-(U5-SPI_CS-Pad9)") (class "Default")
      (node (ref "U5") (pin "9") (pinfunction "SPI_CS_9") (pintype "passive"))
    )
    (net (code "76") (name "unconnected-(U5-SPI_MI_DATA-Pad7)") (class "Default")
      (node (ref "U5") (pin "7") (pinfunction "SPI_MI_DATA_7") (pintype "passive"))
    )
    (net (code "77") (name "unconnected-(U5-SPI_MO_DATA-Pad8)") (class "Default")
      (node (ref "U5") (pin "8") (pinfunction "SPI_MO_DATA_8") (pintype "passive"))
    )
    (net (code "78") (name "unconnected-(U5-STATUS-Pad49)") (class "Default")
      (node (ref "U5") (pin "49") (pinfunction "STATUS_49") (pintype "passive"))
    )
    (net (code "79") (name "unconnected-(U5-UART_CTS-Pad67)") (class "Default")
      (node (ref "U5") (pin "67") (pinfunction "UART_CTS_67") (pintype "passive"))
    )
    (net (code "80") (name "unconnected-(U5-UART_DCD-Pad70)") (class "Default")
      (node (ref "U5") (pin "70") (pinfunction "UART_DCD_70") (pintype "passive"))
    )
    (net (code "81") (name "unconnected-(U5-UART_RI-Pad69)") (class "Default")
      (node (ref "U5") (pin "69") (pinfunction "UART_RI_69") (pintype "passive"))
    )
    (net (code "82") (name "unconnected-(U5-UART_RTS-Pad66)") (class "Default")
      (node (ref "U5") (pin "66") (pinfunction "UART_RTS_66") (pintype "passive"))
    )
    (net (code "83") (name "unconnected-(U5-USB_ID-Pad16)") (class "Default")
      (node (ref "U5") (pin "16") (pinfunction "USB_ID_16") (pintype "passive"))
    )
    (net (code "84") (name "unconnected-(U5-USIM_DET-Pad53)") (class "Default")
      (node (ref "U5") (pin "53") (pinfunction "USIM_DET_53") (pintype "passive"))
    )
    (net (code "85") (name "unconnected-(U5-VDD_EXT-Pad44)") (class "Default")
      (node (ref "U5") (pin "44") (pinfunction "VDD_EXT_44") (pintype "passive"))
    )
    (net (code "86") (name "unconnected-(U11-NC-Pad4)") (class "Default")
      (node (ref "U11") (pin "4") (pinfunction "NC_4") (pintype "passive"))
    )
  )
)
